# KegWasher_1_11_HCRelay_Schematic_EasyEDA.net
KiCad netlist of a schematic drawn in EasyEDA
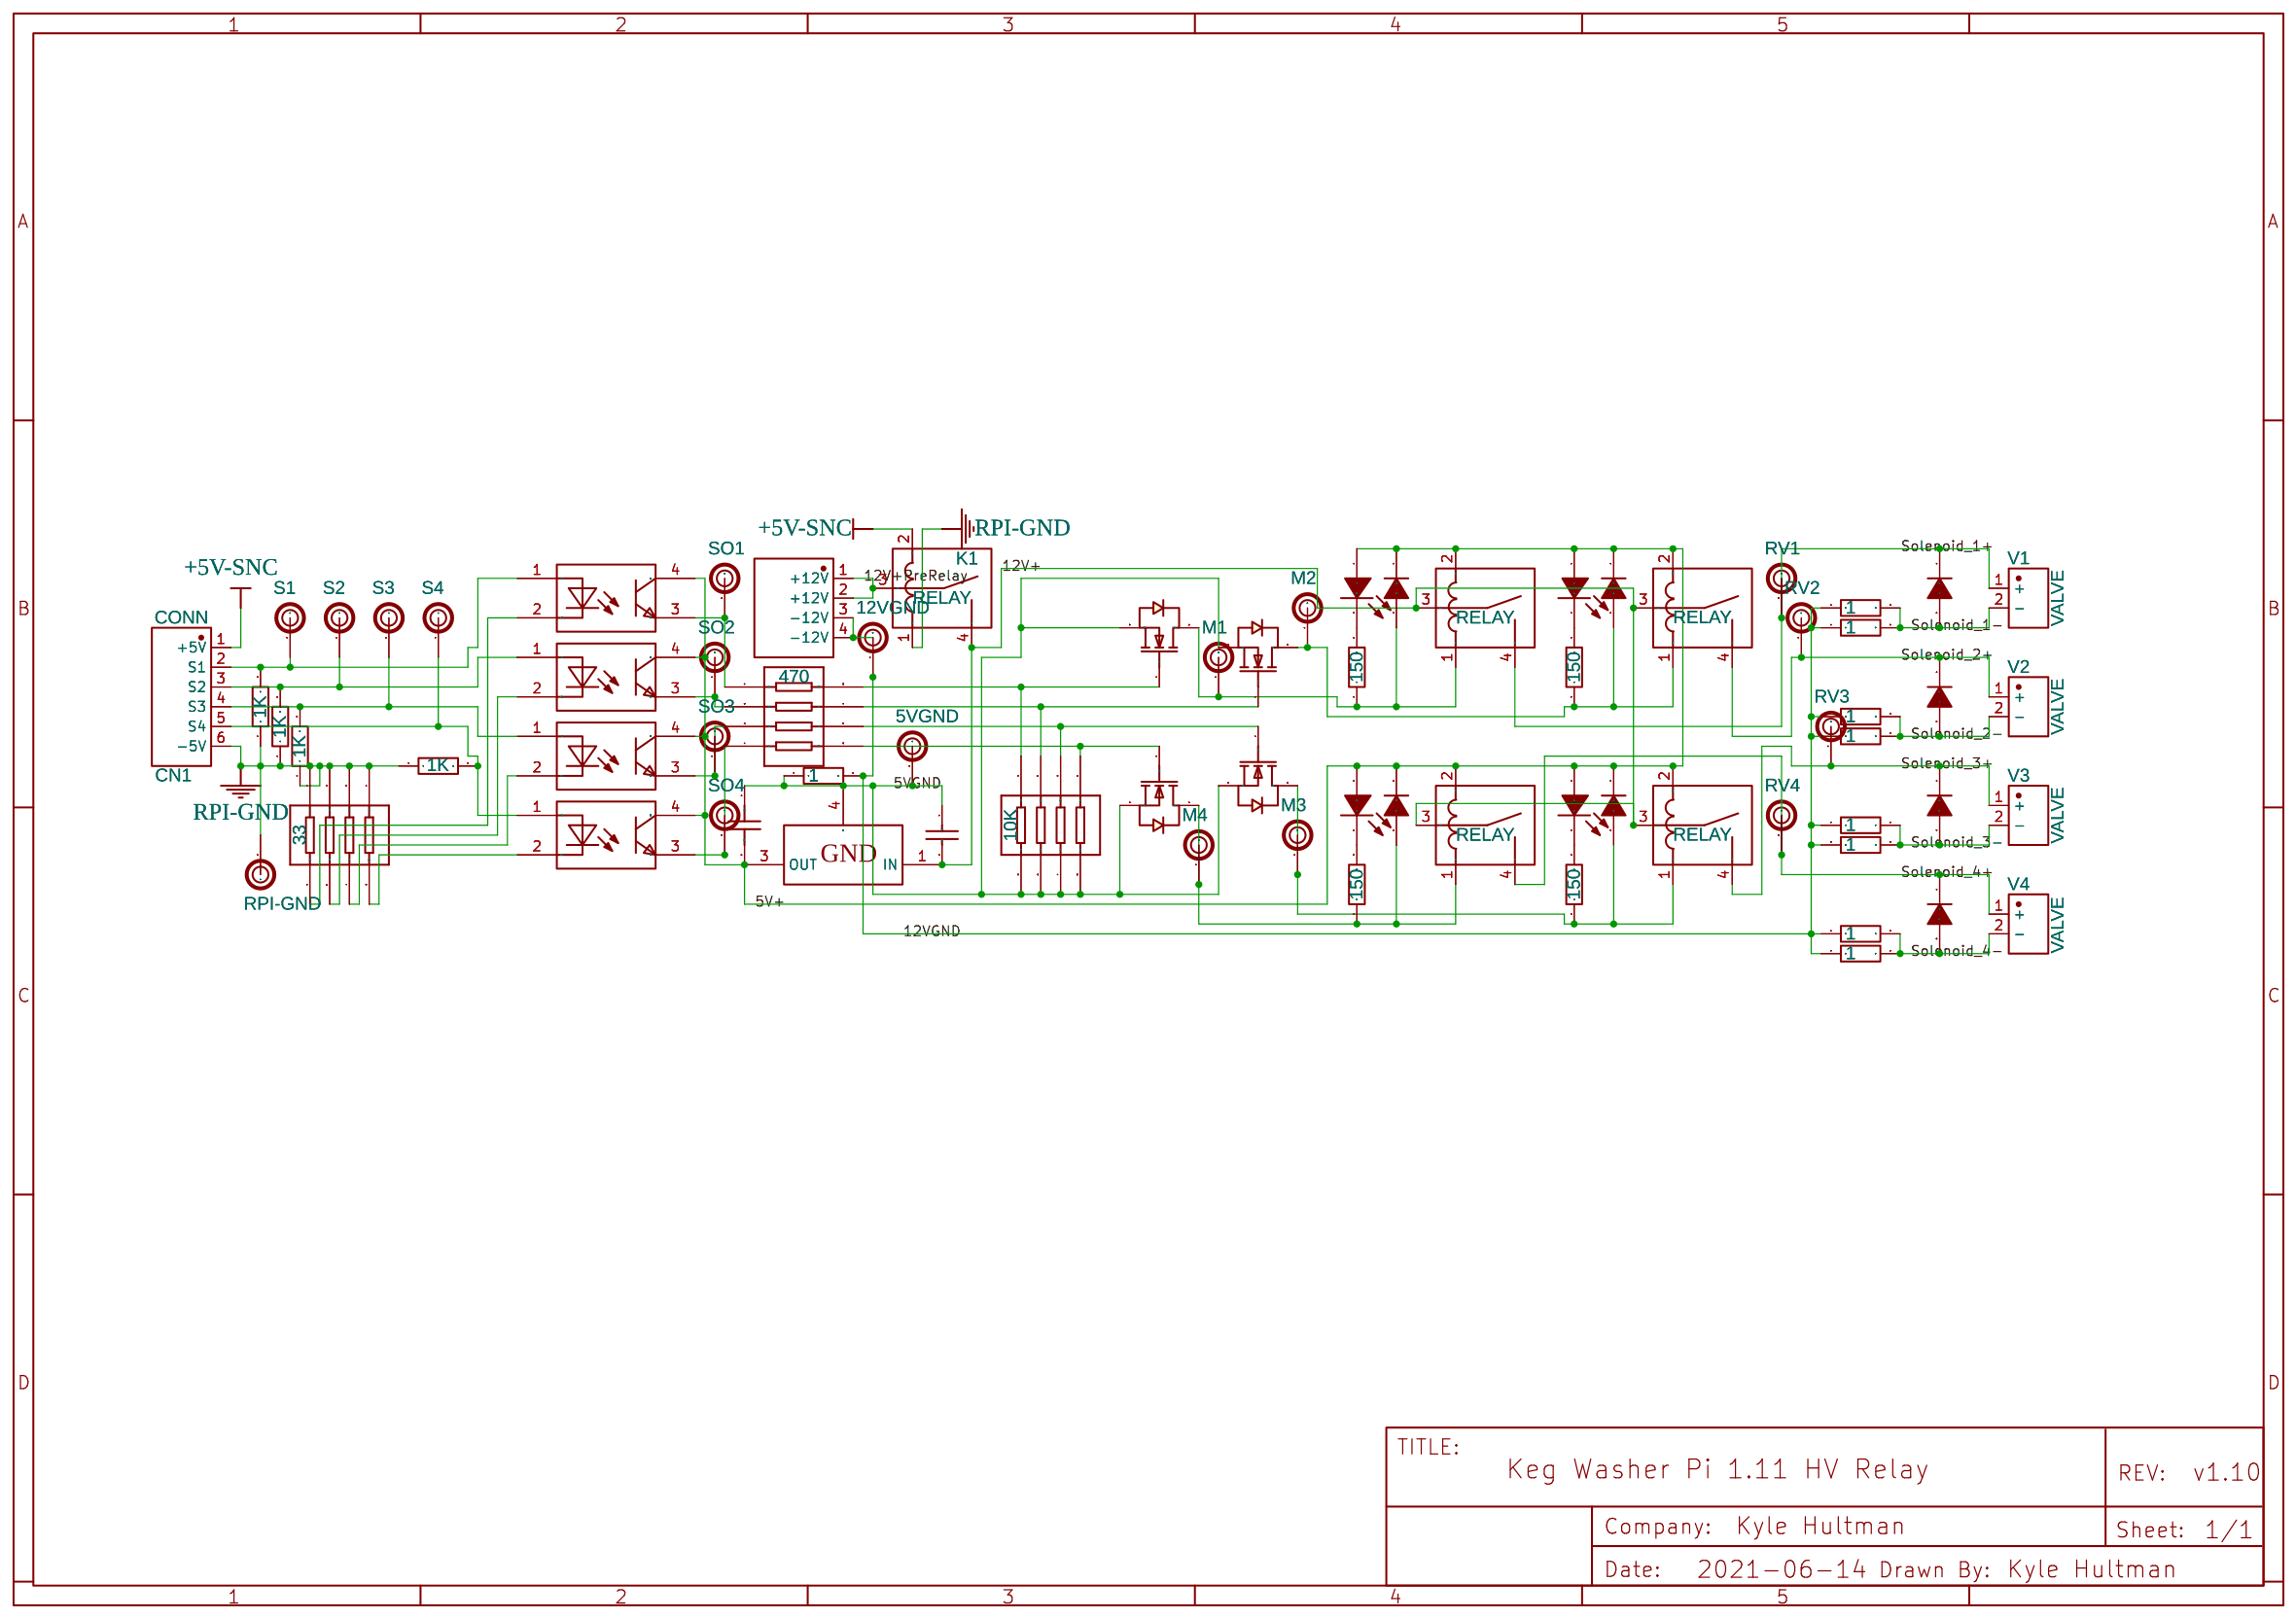
[diagram p0: schematic sheet]

(export (version "E")
  (design (tool "Eeschema 10.0.6"))
  (components
    (comp (ref "5VGND") (value "TestPoint") (libsource (lib "") (part "TestPoint_4")))
    (comp (ref "12VGND") (value "TestPoint") (libsource (lib "") (part "TestPoint_5")))
    (comp (ref "C1")
      (value "330nF")
      (fields
        (field (name "BOM_Manufacturer Part") "0805B334K500NT")
        (field (name "BOM_Supplier Part") "C1740")
      )
      (libsource (lib "") (part "0805B334K500NT"))
    )
    (comp (ref "C2")
      (value "100nF")
      (fields
        (field (name "BOM_Manufacturer Part") "CC0603KRX7R9BB104")
        (field (name "BOM_Supplier Part") "C14663")
      )
      (libsource (lib "") (part "CC0603KRX7R9BB104"))
    )
    (comp (ref "CN1") (value "CONN") (libsource (lib "") (part "CONN")))
    (comp (ref "D1")
      (value "1N4148WS T4")
      (fields (field (name "BOM_Supplier Part") "C2128"))
      (libsource (lib "") (part "1N4148WS T4"))
    )
    (comp (ref "D2")
      (value "1N4148WS T4")
      (fields (field (name "BOM_Supplier Part") "C2128"))
      (libsource (lib "") (part "1N4148WS T4"))
    )
    (comp (ref "D3")
      (value "1N4148WS T4")
      (fields (field (name "BOM_Supplier Part") "C2128"))
      (libsource (lib "") (part "1N4148WS T4"))
    )
    (comp (ref "D4")
      (value "1N4148WS T4")
      (fields (field (name "BOM_Supplier Part") "C2128"))
      (libsource (lib "") (part "1N4148WS T4"))
    )
    (comp (ref "D5")
      (value "1N4148WS T4")
      (fields (field (name "BOM_Supplier Part") "C2128"))
      (libsource (lib "") (part "1N4148WS T4"))
    )
    (comp (ref "D6")
      (value "1N4148WS T4")
      (fields (field (name "BOM_Supplier Part") "C2128"))
      (libsource (lib "") (part "1N4148WS T4"))
    )
    (comp (ref "D7")
      (value "1N4148WS T4")
      (fields (field (name "BOM_Supplier Part") "C2128"))
      (libsource (lib "") (part "1N4148WS T4"))
    )
    (comp (ref "D8")
      (value "1N4148WS T4")
      (fields (field (name "BOM_Supplier Part") "C2128"))
      (libsource (lib "") (part "1N4148WS T4"))
    )
    (comp (ref "K1")
      (value "RELAY")
      (fields
        (field (name "BOM_Manufacturer Part") "CMA51H-S-DC5V-A")
        (field (name "BOM_Supplier Part") "C125687")
      )
      (libsource (lib "") (part "CMA51H-S-DC5V-A"))
    )
    (comp (ref "K2")
      (value "RELAY")
      (fields
        (field (name "BOM_Manufacturer Part") "CMA51H-S-DC5V-A")
        (field (name "BOM_Supplier Part") "C125687")
      )
      (libsource (lib "") (part "CMA51H-S-DC5V-A"))
    )
    (comp (ref "K3")
      (value "RELAY")
      (fields
        (field (name "BOM_Manufacturer Part") "CMA51H-S-DC5V-A")
        (field (name "BOM_Supplier Part") "C125687")
      )
      (libsource (lib "") (part "CMA51H-S-DC5V-A"))
    )
    (comp (ref "K4")
      (value "RELAY")
      (fields
        (field (name "BOM_Manufacturer Part") "CMA51H-S-DC5V-A")
        (field (name "BOM_Supplier Part") "C125687")
      )
      (libsource (lib "") (part "CMA51H-S-DC5V-A"))
    )
    (comp (ref "K5")
      (value "RELAY")
      (fields
        (field (name "BOM_Manufacturer Part") "CMA51H-S-DC5V-A")
        (field (name "BOM_Supplier Part") "C125687")
      )
      (libsource (lib "") (part "CMA51H-S-DC5V-A"))
    )
    (comp (ref "LED9")
      (value "KT-0603R")
      (fields (field (name "BOM_Supplier Part") "C2286"))
      (libsource (lib "") (part "KT-0603R"))
    )
    (comp (ref "LED10")
      (value "KT-0603R")
      (fields (field (name "BOM_Supplier Part") "C2286"))
      (libsource (lib "") (part "KT-0603R"))
    )
    (comp (ref "LED11")
      (value "KT-0603R")
      (fields (field (name "BOM_Supplier Part") "C2286"))
      (libsource (lib "") (part "KT-0603R"))
    )
    (comp (ref "LED12")
      (value "KT-0603R")
      (fields (field (name "BOM_Supplier Part") "C2286"))
      (libsource (lib "") (part "KT-0603R"))
    )
    (comp (ref "M1") (value "TestPoint") (libsource (lib "") (part "TestPoint_1")))
    (comp (ref "M2") (value "TestPoint") (libsource (lib "") (part "TestPoint_1")))
    (comp (ref "M3") (value "TestPoint") (libsource (lib "") (part "TestPoint_1")))
    (comp (ref "M4") (value "TestPoint") (libsource (lib "") (part "TestPoint_1")))
    (comp (ref "PWR1") (value "12vHC-IN") (libsource (lib "") (part "12vHC-IN")))
    (comp (ref "Q1")
      (value "AO3400A")
      (fields (field (name "BOM_Supplier Part") "C20917"))
      (libsource (lib "") (part "AO3400A_1"))
    )
    (comp (ref "Q2")
      (value "AO3400A")
      (fields (field (name "BOM_Supplier Part") "C20917"))
      (libsource (lib "") (part "AO3400A_1"))
    )
    (comp (ref "Q3")
      (value "AO3400A")
      (fields (field (name "BOM_Supplier Part") "C20917"))
      (libsource (lib "") (part "AO3400A"))
    )
    (comp (ref "Q4")
      (value "AO3400A")
      (fields (field (name "BOM_Supplier Part") "C20917"))
      (libsource (lib "") (part "AO3400A"))
    )
    (comp (ref "R1")
      (value "150")
      (fields
        (field (name "BOM_Manufacturer Part") "0603WAF1500T5E")
        (field (name "BOM_Supplier Part") "C22808")
      )
      (libsource (lib "") (part "0603WAF1500T5E"))
    )
    (comp (ref "R2")
      (value "150")
      (fields
        (field (name "BOM_Manufacturer Part") "0603WAF1500T5E")
        (field (name "BOM_Supplier Part") "C22808")
      )
      (libsource (lib "") (part "0603WAF1500T5E"))
    )
    (comp (ref "R3")
      (value "150")
      (fields
        (field (name "BOM_Manufacturer Part") "0603WAF1500T5E")
        (field (name "BOM_Supplier Part") "C22808")
      )
      (libsource (lib "") (part "0603WAF1500T5E"))
    )
    (comp (ref "R4")
      (value "150")
      (fields
        (field (name "BOM_Manufacturer Part") "0603WAF1500T5E")
        (field (name "BOM_Supplier Part") "C22808")
      )
      (libsource (lib "") (part "0603WAF1500T5E"))
    )
    (comp (ref "R5")
      (value "1K")
      (fields
        (field (name "BOM_Manufacturer Part") "0402WGF1001TCE")
        (field (name "BOM_Supplier Part") "C11702")
      )
      (libsource (lib "") (part "0402WGF1001TCE"))
    )
    (comp (ref "R6")
      (value "1K")
      (fields
        (field (name "BOM_Manufacturer Part") "0402WGF1001TCE")
        (field (name "BOM_Supplier Part") "C11702")
      )
      (libsource (lib "") (part "0402WGF1001TCE"))
    )
    (comp (ref "R7")
      (value "1K")
      (fields
        (field (name "BOM_Manufacturer Part") "0402WGF1001TCE")
        (field (name "BOM_Supplier Part") "C11702")
      )
      (libsource (lib "") (part "0402WGF1001TCE"))
    )
    (comp (ref "R8")
      (value "1K")
      (fields
        (field (name "BOM_Manufacturer Part") "0402WGF1001TCE")
        (field (name "BOM_Supplier Part") "C11702")
      )
      (libsource (lib "") (part "0402WGF1001TCE_1"))
    )
    (comp (ref "R9")
      (value "1")
      (fields
        (field (name "BOM_Manufacturer Part") "1206W4F100KT5E")
        (field (name "BOM_Supplier Part") "C17928")
      )
      (libsource (lib "") (part "1206W4F100KT5E"))
    )
    (comp (ref "R10")
      (value "1")
      (fields
        (field (name "BOM_Manufacturer Part") "1206W4F100KT5E")
        (field (name "BOM_Supplier Part") "C17928")
      )
      (libsource (lib "") (part "1206W4F100KT5E"))
    )
    (comp (ref "R11")
      (value "1")
      (fields
        (field (name "BOM_Manufacturer Part") "1206W4F100KT5E")
        (field (name "BOM_Supplier Part") "C17928")
      )
      (libsource (lib "") (part "1206W4F100KT5E"))
    )
    (comp (ref "R12")
      (value "1")
      (fields
        (field (name "BOM_Manufacturer Part") "1206W4F100KT5E")
        (field (name "BOM_Supplier Part") "C17928")
      )
      (libsource (lib "") (part "1206W4F100KT5E"))
    )
    (comp (ref "R13")
      (value "1")
      (fields
        (field (name "BOM_Manufacturer Part") "1206W4F100KT5E")
        (field (name "BOM_Supplier Part") "C17928")
      )
      (libsource (lib "") (part "1206W4F100KT5E"))
    )
    (comp (ref "R14")
      (value "1")
      (fields
        (field (name "BOM_Manufacturer Part") "1206W4F100KT5E")
        (field (name "BOM_Supplier Part") "C17928")
      )
      (libsource (lib "") (part "1206W4F100KT5E"))
    )
    (comp (ref "R15")
      (value "1")
      (fields
        (field (name "BOM_Manufacturer Part") "1206W4F100KT5E")
        (field (name "BOM_Supplier Part") "C17928")
      )
      (libsource (lib "") (part "1206W4F100KT5E"))
    )
    (comp (ref "R16")
      (value "1")
      (fields
        (field (name "BOM_Manufacturer Part") "1206W4F100KT5E")
        (field (name "BOM_Supplier Part") "C17928")
      )
      (libsource (lib "") (part "1206W4F100KT5E"))
    )
    (comp (ref "R17")
      (value "1")
      (fields
        (field (name "BOM_Manufacturer Part") "1206W4F100KT5E")
        (field (name "BOM_Supplier Part") "C17928")
      )
      (libsource (lib "") (part "1206W4F100KT5E"))
    )
    (comp (ref "RN1")
      (value "33")
      (fields
        (field (name "BOM_Manufacturer Part") "4D02WGJ0330TCE")
        (field (name "BOM_Supplier Part") "C25501")
      )
      (libsource (lib "") (part "4D02WGJ0330TCE"))
    )
    (comp (ref "RN2")
      (value "470")
      (fields
        (field (name "BOM_Manufacturer Part") "4D03WGJ0471T5E")
        (field (name "BOM_Supplier Part") "C25510")
      )
      (libsource (lib "") (part "4D03WGJ0471T5E"))
    )
    (comp (ref "RN3")
      (value "10K")
      (fields
        (field (name "BOM_Manufacturer Part") "4D02WGJ0103TCE")
        (field (name "BOM_Supplier Part") "C25725")
      )
      (libsource (lib "") (part "4D02WGJ0103TCE"))
    )
    (comp (ref "RPI-GND") (value "TestPoint") (libsource (lib "") (part "TestPoint_6")))
    (comp (ref "RV1") (value "TestPoint") (libsource (lib "") (part "TestPoint")))
    (comp (ref "RV2") (value "TestPoint") (libsource (lib "") (part "TestPoint")))
    (comp (ref "RV3") (value "TestPoint") (libsource (lib "") (part "TestPoint")))
    (comp (ref "RV4") (value "TestPoint") (libsource (lib "") (part "TestPoint")))
    (comp (ref "S1") (value "TestPoint") (libsource (lib "") (part "TestPoint_2")))
    (comp (ref "S2") (value "TestPoint") (libsource (lib "") (part "TestPoint_2")))
    (comp (ref "S3") (value "TestPoint") (libsource (lib "") (part "TestPoint_2")))
    (comp (ref "S4") (value "TestPoint") (libsource (lib "") (part "TestPoint_2")))
    (comp (ref "SO1") (value "TestPoint") (libsource (lib "") (part "TestPoint_3")))
    (comp (ref "SO2") (value "TestPoint") (libsource (lib "") (part "TestPoint_3")))
    (comp (ref "SO3") (value "TestPoint") (libsource (lib "") (part "TestPoint_3")))
    (comp (ref "SO4") (value "TestPoint") (libsource (lib "") (part "TestPoint_3")))
    (comp (ref "U1")
      (value "EL357N(B)(TA)-G")
      (fields (field (name "BOM_Supplier Part") "C6649"))
      (libsource (lib "") (part "EL357N(B)(TA)-G"))
    )
    (comp (ref "U2")
      (value "EL357N(B)(TA)-G")
      (fields (field (name "BOM_Supplier Part") "C6649"))
      (libsource (lib "") (part "EL357N(B)(TA)-G"))
    )
    (comp (ref "U3")
      (value "EL357N(B)(TA)-G")
      (fields (field (name "BOM_Supplier Part") "C6649"))
      (libsource (lib "") (part "EL357N(B)(TA)-G"))
    )
    (comp (ref "U4")
      (value "EL357N(B)(TA)-G")
      (fields (field (name "BOM_Supplier Part") "C6649"))
      (libsource (lib "") (part "EL357N(B)(TA)-G"))
    )
    (comp (ref "U5")
      (value "L78M05ABDT-TR")
      (fields (field (name "BOM_Supplier Part") "C58069"))
      (libsource (lib "") (part "L78M05ABDT-TR"))
    )
    (comp (ref "V1") (value "VALVE") (libsource (lib "") (part "VALVE")))
    (comp (ref "V2") (value "VALVE") (libsource (lib "") (part "VALVE")))
    (comp (ref "V3") (value "VALVE") (libsource (lib "") (part "VALVE")))
    (comp (ref "V4") (value "VALVE") (libsource (lib "") (part "RELAY")))
  )
  (nets
    (net (code "1") (name "+5V-SNC") (class "Default")
      (node (ref "CN1") (pin "1") (pinfunction "+5V_1") (pintype "passive"))
      (node (ref "K1") (pin "2") (pinfunction "2_2") (pintype "unspecified"))
    )
    (net (code "2") (name "/5V+") (class "Default")
      (node (ref "C2") (pin "2") (pinfunction "2_2") (pintype "unspecified"))
      (node (ref "D1") (pin "1") (pinfunction "K_1") (pintype "unspecified"))
      (node (ref "D2") (pin "1") (pinfunction "K_1") (pintype "unspecified"))
      (node (ref "D3") (pin "1") (pinfunction "K_1") (pintype "unspecified"))
      (node (ref "D4") (pin "1") (pinfunction "K_1") (pintype "unspecified"))
      (node (ref "K2") (pin "2") (pinfunction "2_2") (pintype "unspecified"))
      (node (ref "K3") (pin "2") (pinfunction "2_2") (pintype "unspecified"))
      (node (ref "K4") (pin "2") (pinfunction "2_2") (pintype "unspecified"))
      (node (ref "K5") (pin "2") (pinfunction "2_2") (pintype "unspecified"))
      (node (ref "LED10") (pin "1") (pinfunction "A_1") (pintype "unspecified"))
      (node (ref "LED11") (pin "1") (pinfunction "A_1") (pintype "unspecified"))
      (node (ref "LED12") (pin "1") (pinfunction "A_1") (pintype "unspecified"))
      (node (ref "LED9") (pin "1") (pinfunction "A_1") (pintype "unspecified"))
      (node (ref "U1") (pin "4") (pinfunction "COL_4") (pintype "unspecified"))
      (node (ref "U2") (pin "4") (pinfunction "COL_4") (pintype "unspecified"))
      (node (ref "U3") (pin "4") (pinfunction "COL_4") (pintype "unspecified"))
      (node (ref "U4") (pin "4") (pinfunction "COL_4") (pintype "unspecified"))
      (node (ref "U5") (pin "3") (pinfunction "OUT_3") (pintype "passive"))
    )
    (net (code "3") (name "/5VGND") (class "Default")
      (node (ref "5VGND") (pin "1") (pinfunction "1_1") (pintype "output"))
      (node (ref "C1") (pin "1") (pinfunction "1_1") (pintype "input"))
      (node (ref "C2") (pin "1") (pinfunction "1_1") (pintype "unspecified"))
      (node (ref "Q1") (pin "2") (pinfunction "S_2") (pintype "unspecified"))
      (node (ref "Q2") (pin "2") (pinfunction "S_2") (pintype "unspecified"))
      (node (ref "Q3") (pin "2") (pinfunction "S_2") (pintype "unspecified"))
      (node (ref "Q4") (pin "2") (pinfunction "S_2") (pintype "unspecified"))
      (node (ref "R17") (pin "1") (pinfunction "1_1") (pintype "input"))
      (node (ref "RN3") (pin "5") (pinfunction "5_5") (pintype "input"))
      (node (ref "RN3") (pin "6") (pinfunction "6_6") (pintype "input"))
      (node (ref "RN3") (pin "7") (pinfunction "7_7") (pintype "input"))
      (node (ref "RN3") (pin "8") (pinfunction "8_8") (pintype "input"))
      (node (ref "U5") (pin "4") (pinfunction "GND_4") (pintype "passive"))
    )
    (net (code "4") (name "/12V+") (class "Default")
      (node (ref "C1") (pin "2") (pinfunction "2_2") (pintype "input"))
      (node (ref "K1") (pin "4") (pinfunction "4_4") (pintype "unspecified"))
      (node (ref "K2") (pin "3") (pinfunction "3_3") (pintype "unspecified"))
      (node (ref "K3") (pin "3") (pinfunction "3_3") (pintype "unspecified"))
      (node (ref "K4") (pin "3") (pinfunction "3_3") (pintype "unspecified"))
      (node (ref "K5") (pin "3") (pinfunction "3_3") (pintype "unspecified"))
      (node (ref "U5") (pin "1") (pinfunction "IN_1") (pintype "passive"))
    )
    (net (code "5") (name "/12V+PreRelay") (class "Default")
      (node (ref "K1") (pin "3") (pinfunction "3_3") (pintype "unspecified"))
      (node (ref "PWR1") (pin "1") (pinfunction "+12V_1") (pintype "passive"))
      (node (ref "PWR1") (pin "2") (pinfunction "+12V_2") (pintype "passive"))
    )
    (net (code "6") (name "/12VGND") (class "Default")
      (node (ref "12VGND") (pin "1") (pinfunction "1_1") (pintype "output"))
      (node (ref "PWR1") (pin "3") (pinfunction "-12V_3") (pintype "passive"))
      (node (ref "PWR1") (pin "4") (pinfunction "-12V_4") (pintype "passive"))
      (node (ref "R10") (pin "1") (pinfunction "1_1") (pintype "input"))
      (node (ref "R11") (pin "1") (pinfunction "1_1") (pintype "input"))
      (node (ref "R12") (pin "1") (pinfunction "1_1") (pintype "input"))
      (node (ref "R13") (pin "1") (pinfunction "1_1") (pintype "input"))
      (node (ref "R14") (pin "1") (pinfunction "1_1") (pintype "input"))
      (node (ref "R15") (pin "1") (pinfunction "1_1") (pintype "input"))
      (node (ref "R16") (pin "1") (pinfunction "1_1") (pintype "input"))
      (node (ref "R17") (pin "2") (pinfunction "2_2") (pintype "input"))
      (node (ref "R9") (pin "1") (pinfunction "1_1") (pintype "input"))
    )
    (net (code "7") (name "/Solenoid_1+") (class "Default")
      (node (ref "D5") (pin "1") (pinfunction "K_1") (pintype "unspecified"))
      (node (ref "K2") (pin "4") (pinfunction "4_4") (pintype "unspecified"))
      (node (ref "RV1") (pin "1") (pinfunction "1_1") (pintype "output"))
      (node (ref "V1") (pin "1") (pinfunction "+_1") (pintype "passive"))
    )
    (net (code "8") (name "/Solenoid_1-") (class "Default")
      (node (ref "D5") (pin "2") (pinfunction "A_2") (pintype "unspecified"))
      (node (ref "R10") (pin "2") (pinfunction "2_2") (pintype "input"))
      (node (ref "R9") (pin "2") (pinfunction "2_2") (pintype "input"))
      (node (ref "V1") (pin "2") (pinfunction "-_2") (pintype "passive"))
    )
    (net (code "9") (name "/Solenoid_2+") (class "Default")
      (node (ref "D6") (pin "1") (pinfunction "K_1") (pintype "unspecified"))
      (node (ref "K3") (pin "4") (pinfunction "4_4") (pintype "unspecified"))
      (node (ref "RV2") (pin "1") (pinfunction "1_1") (pintype "output"))
      (node (ref "V2") (pin "1") (pinfunction "+_1") (pintype "passive"))
    )
    (net (code "10") (name "/Solenoid_2-") (class "Default")
      (node (ref "D6") (pin "2") (pinfunction "A_2") (pintype "unspecified"))
      (node (ref "R11") (pin "2") (pinfunction "2_2") (pintype "input"))
      (node (ref "R12") (pin "2") (pinfunction "2_2") (pintype "input"))
      (node (ref "V2") (pin "2") (pinfunction "-_2") (pintype "passive"))
    )
    (net (code "11") (name "/Solenoid_3+") (class "Default")
      (node (ref "D7") (pin "1") (pinfunction "K_1") (pintype "unspecified"))
      (node (ref "K4") (pin "4") (pinfunction "4_4") (pintype "unspecified"))
      (node (ref "RV3") (pin "1") (pinfunction "1_1") (pintype "output"))
      (node (ref "V3") (pin "1") (pinfunction "+_1") (pintype "passive"))
    )
    (net (code "12") (name "/Solenoid_3-") (class "Default")
      (node (ref "D7") (pin "2") (pinfunction "A_2") (pintype "unspecified"))
      (node (ref "R13") (pin "2") (pinfunction "2_2") (pintype "input"))
      (node (ref "R14") (pin "2") (pinfunction "2_2") (pintype "input"))
      (node (ref "V3") (pin "2") (pinfunction "-_2") (pintype "passive"))
    )
    (net (code "13") (name "/Solenoid_4+") (class "Default")
      (node (ref "D8") (pin "1") (pinfunction "K_1") (pintype "unspecified"))
      (node (ref "K5") (pin "4") (pinfunction "4_4") (pintype "unspecified"))
      (node (ref "RV4") (pin "1") (pinfunction "1_1") (pintype "output"))
      (node (ref "V4") (pin "1") (pinfunction "+_1") (pintype "passive"))
    )
    (net (code "14") (name "/Solenoid_4-") (class "Default")
      (node (ref "D8") (pin "2") (pinfunction "A_2") (pintype "unspecified"))
      (node (ref "R15") (pin "2") (pinfunction "2_2") (pintype "input"))
      (node (ref "R16") (pin "2") (pinfunction "2_2") (pintype "input"))
      (node (ref "V4") (pin "2") (pinfunction "-_2") (pintype "passive"))
    )
    (net (code "15") (name "Net-(CN1-S1)") (class "Default")
      (node (ref "CN1") (pin "2") (pinfunction "S1_2") (pintype "input"))
      (node (ref "R5") (pin "2") (pinfunction "2_2") (pintype "input"))
      (node (ref "S1") (pin "1") (pinfunction "1_1") (pintype "output"))
      (node (ref "U1") (pin "1") (pinfunction "AN_1") (pintype "unspecified"))
    )
    (net (code "16") (name "Net-(CN1-S2)") (class "Default")
      (node (ref "CN1") (pin "3") (pinfunction "S2_3") (pintype "input"))
      (node (ref "R6") (pin "2") (pinfunction "2_2") (pintype "input"))
      (node (ref "S2") (pin "1") (pinfunction "1_1") (pintype "output"))
      (node (ref "U2") (pin "1") (pinfunction "AN_1") (pintype "unspecified"))
    )
    (net (code "17") (name "Net-(CN1-S3)") (class "Default")
      (node (ref "CN1") (pin "4") (pinfunction "S3_4") (pintype "input"))
      (node (ref "R7") (pin "2") (pinfunction "2_2") (pintype "input"))
      (node (ref "S3") (pin "1") (pinfunction "1_1") (pintype "output"))
      (node (ref "U3") (pin "1") (pinfunction "AN_1") (pintype "unspecified"))
    )
    (net (code "18") (name "Net-(CN1-S4)") (class "Default")
      (node (ref "CN1") (pin "5") (pinfunction "S4_5") (pintype "input"))
      (node (ref "R8") (pin "2") (pinfunction "2_2") (pintype "input"))
      (node (ref "S4") (pin "1") (pinfunction "1_1") (pintype "output"))
      (node (ref "U4") (pin "1") (pinfunction "AN_1") (pintype "unspecified"))
    )
    (net (code "19") (name "Net-(D1-A)") (class "Default")
      (node (ref "D1") (pin "2") (pinfunction "A_2") (pintype "unspecified"))
      (node (ref "K2") (pin "1") (pinfunction "1_1") (pintype "unspecified"))
      (node (ref "M1") (pin "1") (pinfunction "1_1") (pintype "output"))
      (node (ref "Q1") (pin "3") (pinfunction "D_3") (pintype "unspecified"))
      (node (ref "R1") (pin "1") (pinfunction "1_1") (pintype "input"))
    )
    (net (code "20") (name "Net-(D2-A)") (class "Default")
      (node (ref "D2") (pin "2") (pinfunction "A_2") (pintype "unspecified"))
      (node (ref "K3") (pin "1") (pinfunction "1_1") (pintype "unspecified"))
      (node (ref "M2") (pin "1") (pinfunction "1_1") (pintype "output"))
      (node (ref "Q2") (pin "3") (pinfunction "D_3") (pintype "unspecified"))
      (node (ref "R2") (pin "1") (pinfunction "1_1") (pintype "input"))
    )
    (net (code "21") (name "Net-(D3-A)") (class "Default")
      (node (ref "D3") (pin "2") (pinfunction "A_2") (pintype "unspecified"))
      (node (ref "K4") (pin "1") (pinfunction "1_1") (pintype "unspecified"))
      (node (ref "M3") (pin "1") (pinfunction "1_1") (pintype "output"))
      (node (ref "Q3") (pin "3") (pinfunction "D_3") (pintype "unspecified"))
      (node (ref "R3") (pin "1") (pinfunction "1_1") (pintype "input"))
    )
    (net (code "22") (name "Net-(D4-A)") (class "Default")
      (node (ref "D4") (pin "2") (pinfunction "A_2") (pintype "unspecified"))
      (node (ref "K5") (pin "1") (pinfunction "1_1") (pintype "unspecified"))
      (node (ref "M4") (pin "1") (pinfunction "1_1") (pintype "output"))
      (node (ref "Q4") (pin "3") (pinfunction "D_3") (pintype "unspecified"))
      (node (ref "R4") (pin "1") (pinfunction "1_1") (pintype "input"))
    )
    (net (code "23") (name "Net-(LED9-K)") (class "Default")
      (node (ref "LED9") (pin "2") (pinfunction "K_2") (pintype "unspecified"))
      (node (ref "R1") (pin "2") (pinfunction "2_2") (pintype "input"))
    )
    (net (code "24") (name "Net-(LED10-K)") (class "Default")
      (node (ref "LED10") (pin "2") (pinfunction "K_2") (pintype "unspecified"))
      (node (ref "R2") (pin "2") (pinfunction "2_2") (pintype "input"))
    )
    (net (code "25") (name "Net-(LED11-K)") (class "Default")
      (node (ref "LED11") (pin "2") (pinfunction "K_2") (pintype "unspecified"))
      (node (ref "R3") (pin "2") (pinfunction "2_2") (pintype "input"))
    )
    (net (code "26") (name "Net-(LED12-K)") (class "Default")
      (node (ref "LED12") (pin "2") (pinfunction "K_2") (pintype "unspecified"))
      (node (ref "R4") (pin "2") (pinfunction "2_2") (pintype "input"))
    )
    (net (code "27") (name "Net-(Q1-G)") (class "Default")
      (node (ref "Q1") (pin "1") (pinfunction "G_1") (pintype "unspecified"))
      (node (ref "RN2") (pin "8") (pinfunction "8_8") (pintype "input"))
      (node (ref "RN3") (pin "4") (pinfunction "4_4") (pintype "input"))
    )
    (net (code "28") (name "Net-(Q2-G)") (class "Default")
      (node (ref "Q2") (pin "1") (pinfunction "G_1") (pintype "unspecified"))
      (node (ref "RN2") (pin "7") (pinfunction "7_7") (pintype "input"))
      (node (ref "RN3") (pin "3") (pinfunction "3_3") (pintype "input"))
    )
    (net (code "29") (name "Net-(Q3-G)") (class "Default")
      (node (ref "Q3") (pin "1") (pinfunction "G_1") (pintype "unspecified"))
      (node (ref "RN2") (pin "6") (pinfunction "6_6") (pintype "input"))
      (node (ref "RN3") (pin "2") (pinfunction "2_2") (pintype "input"))
    )
    (net (code "30") (name "Net-(Q4-G)") (class "Default")
      (node (ref "Q4") (pin "1") (pinfunction "G_1") (pintype "unspecified"))
      (node (ref "RN2") (pin "5") (pinfunction "5_5") (pintype "input"))
      (node (ref "RN3") (pin "1") (pinfunction "1_1") (pintype "input"))
    )
    (net (code "31") (name "Net-(U1-CAT)") (class "Default")
      (node (ref "RN1") (pin "5") (pinfunction "5_5") (pintype "input"))
      (node (ref "U1") (pin "2") (pinfunction "CAT_2") (pintype "unspecified"))
    )
    (net (code "32") (name "Net-(U1-EM)") (class "Default")
      (node (ref "RN2") (pin "1") (pinfunction "1_1") (pintype "input"))
      (node (ref "SO1") (pin "1") (pinfunction "1_1") (pintype "output"))
      (node (ref "U1") (pin "3") (pinfunction "EM_3") (pintype "unspecified"))
    )
    (net (code "33") (name "Net-(U2-CAT)") (class "Default")
      (node (ref "RN1") (pin "6") (pinfunction "6_6") (pintype "input"))
      (node (ref "U2") (pin "2") (pinfunction "CAT_2") (pintype "unspecified"))
    )
    (net (code "34") (name "Net-(U2-EM)") (class "Default")
      (node (ref "RN2") (pin "2") (pinfunction "2_2") (pintype "input"))
      (node (ref "SO2") (pin "1") (pinfunction "1_1") (pintype "output"))
      (node (ref "U2") (pin "3") (pinfunction "EM_3") (pintype "unspecified"))
    )
    (net (code "35") (name "Net-(U3-CAT)") (class "Default")
      (node (ref "RN1") (pin "7") (pinfunction "7_7") (pintype "input"))
      (node (ref "U3") (pin "2") (pinfunction "CAT_2") (pintype "unspecified"))
    )
    (net (code "36") (name "Net-(U3-EM)") (class "Default")
      (node (ref "RN2") (pin "3") (pinfunction "3_3") (pintype "input"))
      (node (ref "SO3") (pin "1") (pinfunction "1_1") (pintype "output"))
      (node (ref "U3") (pin "3") (pinfunction "EM_3") (pintype "unspecified"))
    )
    (net (code "37") (name "Net-(U4-CAT)") (class "Default")
      (node (ref "RN1") (pin "8") (pinfunction "8_8") (pintype "input"))
      (node (ref "U4") (pin "2") (pinfunction "CAT_2") (pintype "unspecified"))
    )
    (net (code "38") (name "Net-(U4-EM)") (class "Default")
      (node (ref "RN2") (pin "4") (pinfunction "4_4") (pintype "input"))
      (node (ref "SO4") (pin "1") (pinfunction "1_1") (pintype "output"))
      (node (ref "U4") (pin "3") (pinfunction "EM_3") (pintype "unspecified"))
    )
    (net (code "39") (name "RPI-GND") (class "Default")
      (node (ref "CN1") (pin "6") (pinfunction "-5V_6") (pintype "passive"))
      (node (ref "K1") (pin "1") (pinfunction "1_1") (pintype "unspecified"))
      (node (ref "R5") (pin "1") (pinfunction "1_1") (pintype "input"))
      (node (ref "R6") (pin "1") (pinfunction "1_1") (pintype "input"))
      (node (ref "R7") (pin "1") (pinfunction "1_1") (pintype "input"))
      (node (ref "R8") (pin "1") (pinfunction "1_1") (pintype "input"))
      (node (ref "RN1") (pin "1") (pinfunction "1_1") (pintype "input"))
      (node (ref "RN1") (pin "2") (pinfunction "2_2") (pintype "input"))
      (node (ref "RN1") (pin "3") (pinfunction "3_3") (pintype "input"))
      (node (ref "RN1") (pin "4") (pinfunction "4_4") (pintype "input"))
      (node (ref "RPI-GND") (pin "1") (pinfunction "1_1") (pintype "output"))
    )
  )
)
